# labortagebadge2013.net
KiCad netlist of a schematic drawn in EAGLE
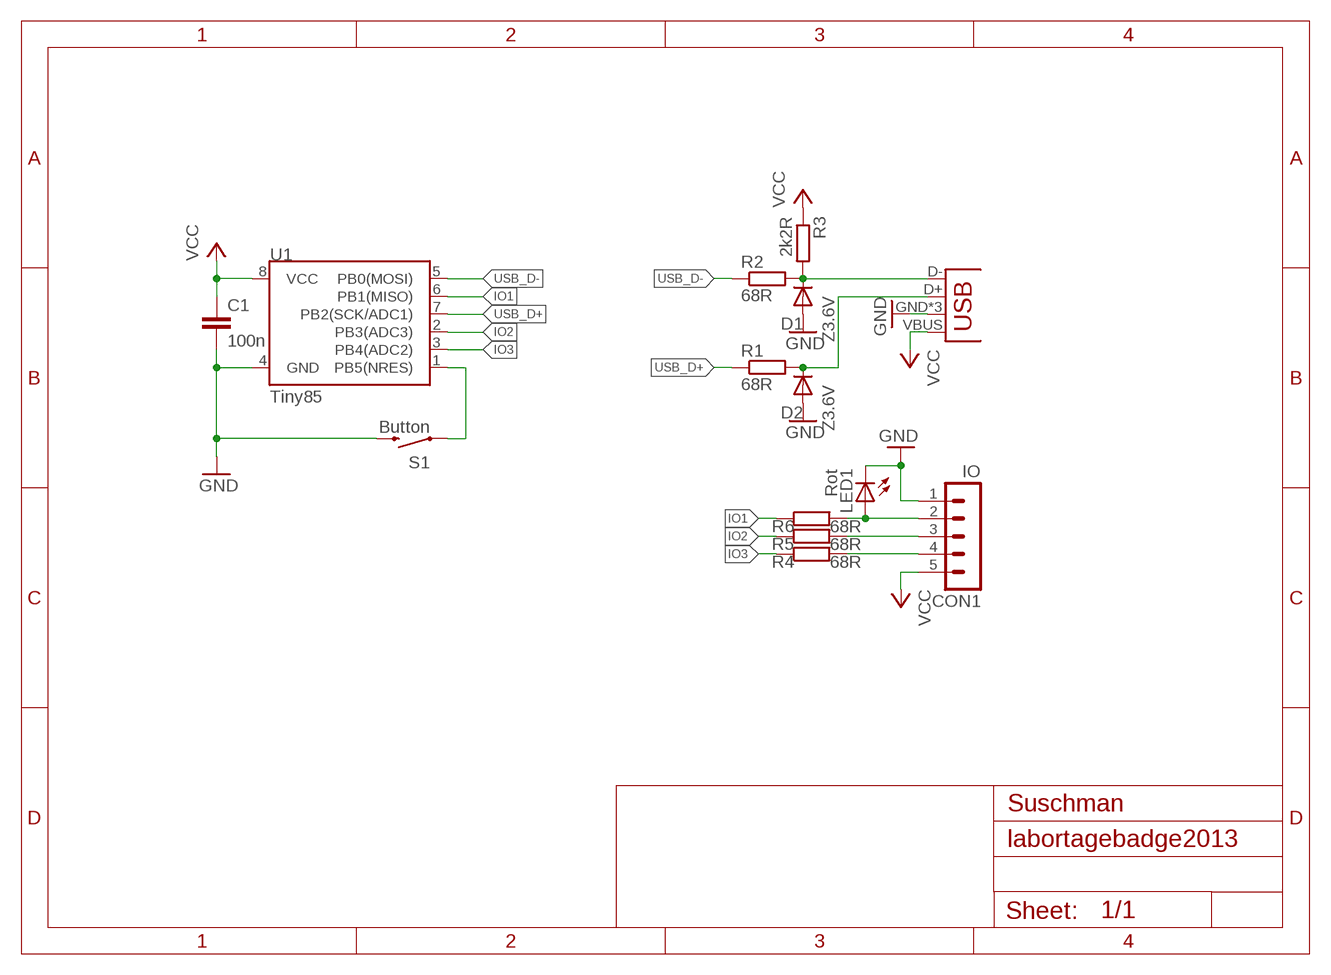
[diagram p0: schematic, sheet 1]

(export (version "E")
  (design (tool "Eeschema 10.0.6"))
  (components
    (comp (ref "C1")
      (value "100n")
      (footprint "eagle-import:C0805")
      (libsource (lib "eagle-import") (part "C-EUC0805"))
    )
    (comp (ref "CON1")
      (value "IO")
      (footprint "eagle-import:MA05-1")
      (libsource (lib "eagle-import") (part "MA05-1"))
    )
    (comp (ref "D1")
      (value "Z3.6V")
      (footprint "eagle-import:MINIMELF")
      (libsource (lib "eagle-import") (part "DIODE-MINIMELF"))
    )
    (comp (ref "D2")
      (value "Z3.6V")
      (footprint "eagle-import:MINIMELF")
      (libsource (lib "eagle-import") (part "DIODE-MINIMELF"))
    )
    (comp (ref "LED1")
      (value "Rot")
      (footprint "eagle-import:CHIPLED_0805")
      (libsource (lib "eagle-import") (part "LEDCHIPLED_0805"))
    )
    (comp (ref "R1")
      (value "68R")
      (footprint "eagle-import:R0805")
      (libsource (lib "eagle-import") (part "R-EU_R0805"))
    )
    (comp (ref "R2")
      (value "68R")
      (footprint "eagle-import:R0805")
      (libsource (lib "eagle-import") (part "R-EU_R0805"))
    )
    (comp (ref "R3")
      (value "2k2R")
      (footprint "eagle-import:R0805")
      (libsource (lib "eagle-import") (part "R-EU_R0805"))
    )
    (comp (ref "R4")
      (value "68R")
      (footprint "eagle-import:R0805")
      (libsource (lib "eagle-import") (part "R-EU_R0805"))
    )
    (comp (ref "R5")
      (value "68R")
      (footprint "eagle-import:R0805")
      (libsource (lib "eagle-import") (part "R-EU_R0805"))
    )
    (comp (ref "R6")
      (value "68R")
      (footprint "eagle-import:R0805")
      (libsource (lib "eagle-import") (part "R-EU_R0805"))
    )
    (comp (ref "S1")
      (value "Button")
      (footprint "eagle-import:TACTILE_SWITCH_TALL")
      (libsource (lib "eagle-import") (part "SWITCH-MOMENTARY-2"))
    )
    (comp (ref "U1")
      (value "Tiny85")
      (footprint "eagle-import:SO08-EIAJ")
      (libsource (lib "eagle-import") (part "ATTINY45TINY85-20-SMT"))
    )
    (comp (ref "USB-A")
      (value "USB-A")
      (footprint "eagle-import:USB-A-H")
      (libsource (lib "eagle-import") (part "USB-A-H"))
    )
  )
  (nets
    (net (code "1") (name "GND") (class "Default")
      (node (ref "C1") (pin "2") (pinfunction "2_2") (pintype "passive"))
      (node (ref "CON1") (pin "1") (pinfunction "1_1") (pintype "passive"))
      (node (ref "D1") (pin "A") (pinfunction "A_A") (pintype "passive"))
      (node (ref "D2") (pin "A") (pinfunction "A_A") (pintype "passive"))
      (node (ref "LED1") (pin "C") (pinfunction "C_C") (pintype "passive"))
      (node (ref "S1") (pin "B1") (pinfunction "2_B1") (pintype "passive"))
      (node (ref "S1") (pin "B2") (pinfunction "2_B2") (pintype "passive"))
      (node (ref "U1") (pin "4") (pinfunction "GND_4") (pintype "bidirectional"))
      (node (ref "USB-A") (pin "GND") (pinfunction "VBUS_GND") (pintype "bidirectional"))
      (node (ref "USB-A") (pin "GND2") (pinfunction "VBUS_GND2") (pintype "bidirectional"))
      (node (ref "USB-A") (pin "GND3") (pinfunction "VBUS_GND3") (pintype "bidirectional"))
    )
    (net (code "2") (name "IO1") (class "Default")
      (node (ref "R6") (pin "1") (pinfunction "1_1") (pintype "passive"))
      (node (ref "U1") (pin "6") (pinfunction "PB1(MISO)_6") (pintype "bidirectional"))
    )
    (net (code "3") (name "IO2") (class "Default")
      (node (ref "R5") (pin "1") (pinfunction "1_1") (pintype "passive"))
      (node (ref "U1") (pin "2") (pinfunction "PB3(ADC3)_2") (pintype "bidirectional"))
    )
    (net (code "4") (name "IO3") (class "Default")
      (node (ref "R4") (pin "1") (pinfunction "1_1") (pintype "passive"))
      (node (ref "U1") (pin "3") (pinfunction "PB4(ADC2)_3") (pintype "bidirectional"))
    )
    (net (code "5") (name "Net-(CON1-Pad2)") (class "Default")
      (node (ref "CON1") (pin "2") (pinfunction "2_2") (pintype "passive"))
      (node (ref "LED1") (pin "A") (pinfunction "A_A") (pintype "passive"))
      (node (ref "R6") (pin "2") (pinfunction "2_2") (pintype "passive"))
    )
    (net (code "6") (name "Net-(CON1-Pad3)") (class "Default")
      (node (ref "CON1") (pin "3") (pinfunction "3_3") (pintype "passive"))
      (node (ref "R5") (pin "2") (pinfunction "2_2") (pintype "passive"))
    )
    (net (code "7") (name "Net-(CON1-Pad4)") (class "Default")
      (node (ref "CON1") (pin "4") (pinfunction "4_4") (pintype "passive"))
      (node (ref "R4") (pin "2") (pinfunction "2_2") (pintype "passive"))
    )
    (net (code "8") (name "Net-(U1-PB5(NRES))") (class "Default")
      (node (ref "S1") (pin "A1") (pinfunction "1_A1") (pintype "passive"))
      (node (ref "S1") (pin "A2") (pinfunction "1_A2") (pintype "passive"))
      (node (ref "U1") (pin "1") (pinfunction "PB5(NRES)_1") (pintype "bidirectional"))
    )
    (net (code "9") (name "Net-(USB-A-D+)") (class "Default")
      (node (ref "D1") (pin "C") (pinfunction "C_C") (pintype "passive"))
      (node (ref "R2") (pin "2") (pinfunction "2_2") (pintype "passive"))
      (node (ref "R3") (pin "2") (pinfunction "2_2") (pintype "passive"))
      (node (ref "USB-A") (pin "D-") (pinfunction "D+_D-") (pintype "bidirectional"))
    )
    (net (code "10") (name "Net-(USB-A-D-)") (class "Default")
      (node (ref "D2") (pin "C") (pinfunction "C_C") (pintype "passive"))
      (node (ref "R1") (pin "2") (pinfunction "2_2") (pintype "passive"))
      (node (ref "USB-A") (pin "D+") (pinfunction "D-_D+") (pintype "bidirectional"))
    )
    (net (code "11") (name "USB_D+") (class "Default")
      (node (ref "R1") (pin "1") (pinfunction "1_1") (pintype "passive"))
      (node (ref "U1") (pin "7") (pinfunction "PB2(SCK/ADC1)_7") (pintype "bidirectional"))
    )
    (net (code "12") (name "USB_D-") (class "Default")
      (node (ref "R2") (pin "1") (pinfunction "1_1") (pintype "passive"))
      (node (ref "U1") (pin "5") (pinfunction "PB0(MOSI)_5") (pintype "bidirectional"))
    )
    (net (code "13") (name "VCC") (class "Default")
      (node (ref "C1") (pin "1") (pinfunction "1_1") (pintype "passive"))
      (node (ref "CON1") (pin "5") (pinfunction "5_5") (pintype "passive"))
      (node (ref "R3") (pin "1") (pinfunction "1_1") (pintype "passive"))
      (node (ref "U1") (pin "8") (pinfunction "VCC_8") (pintype "bidirectional"))
      (node (ref "USB-A") (pin "VBUS") (pinfunction "GND_VBUS") (pintype "bidirectional"))
    )
  )
)
